# SCH_PCB_sin_SMD-v1_2026-09-21.net
KiCad netlist of a schematic drawn in EasyEDA
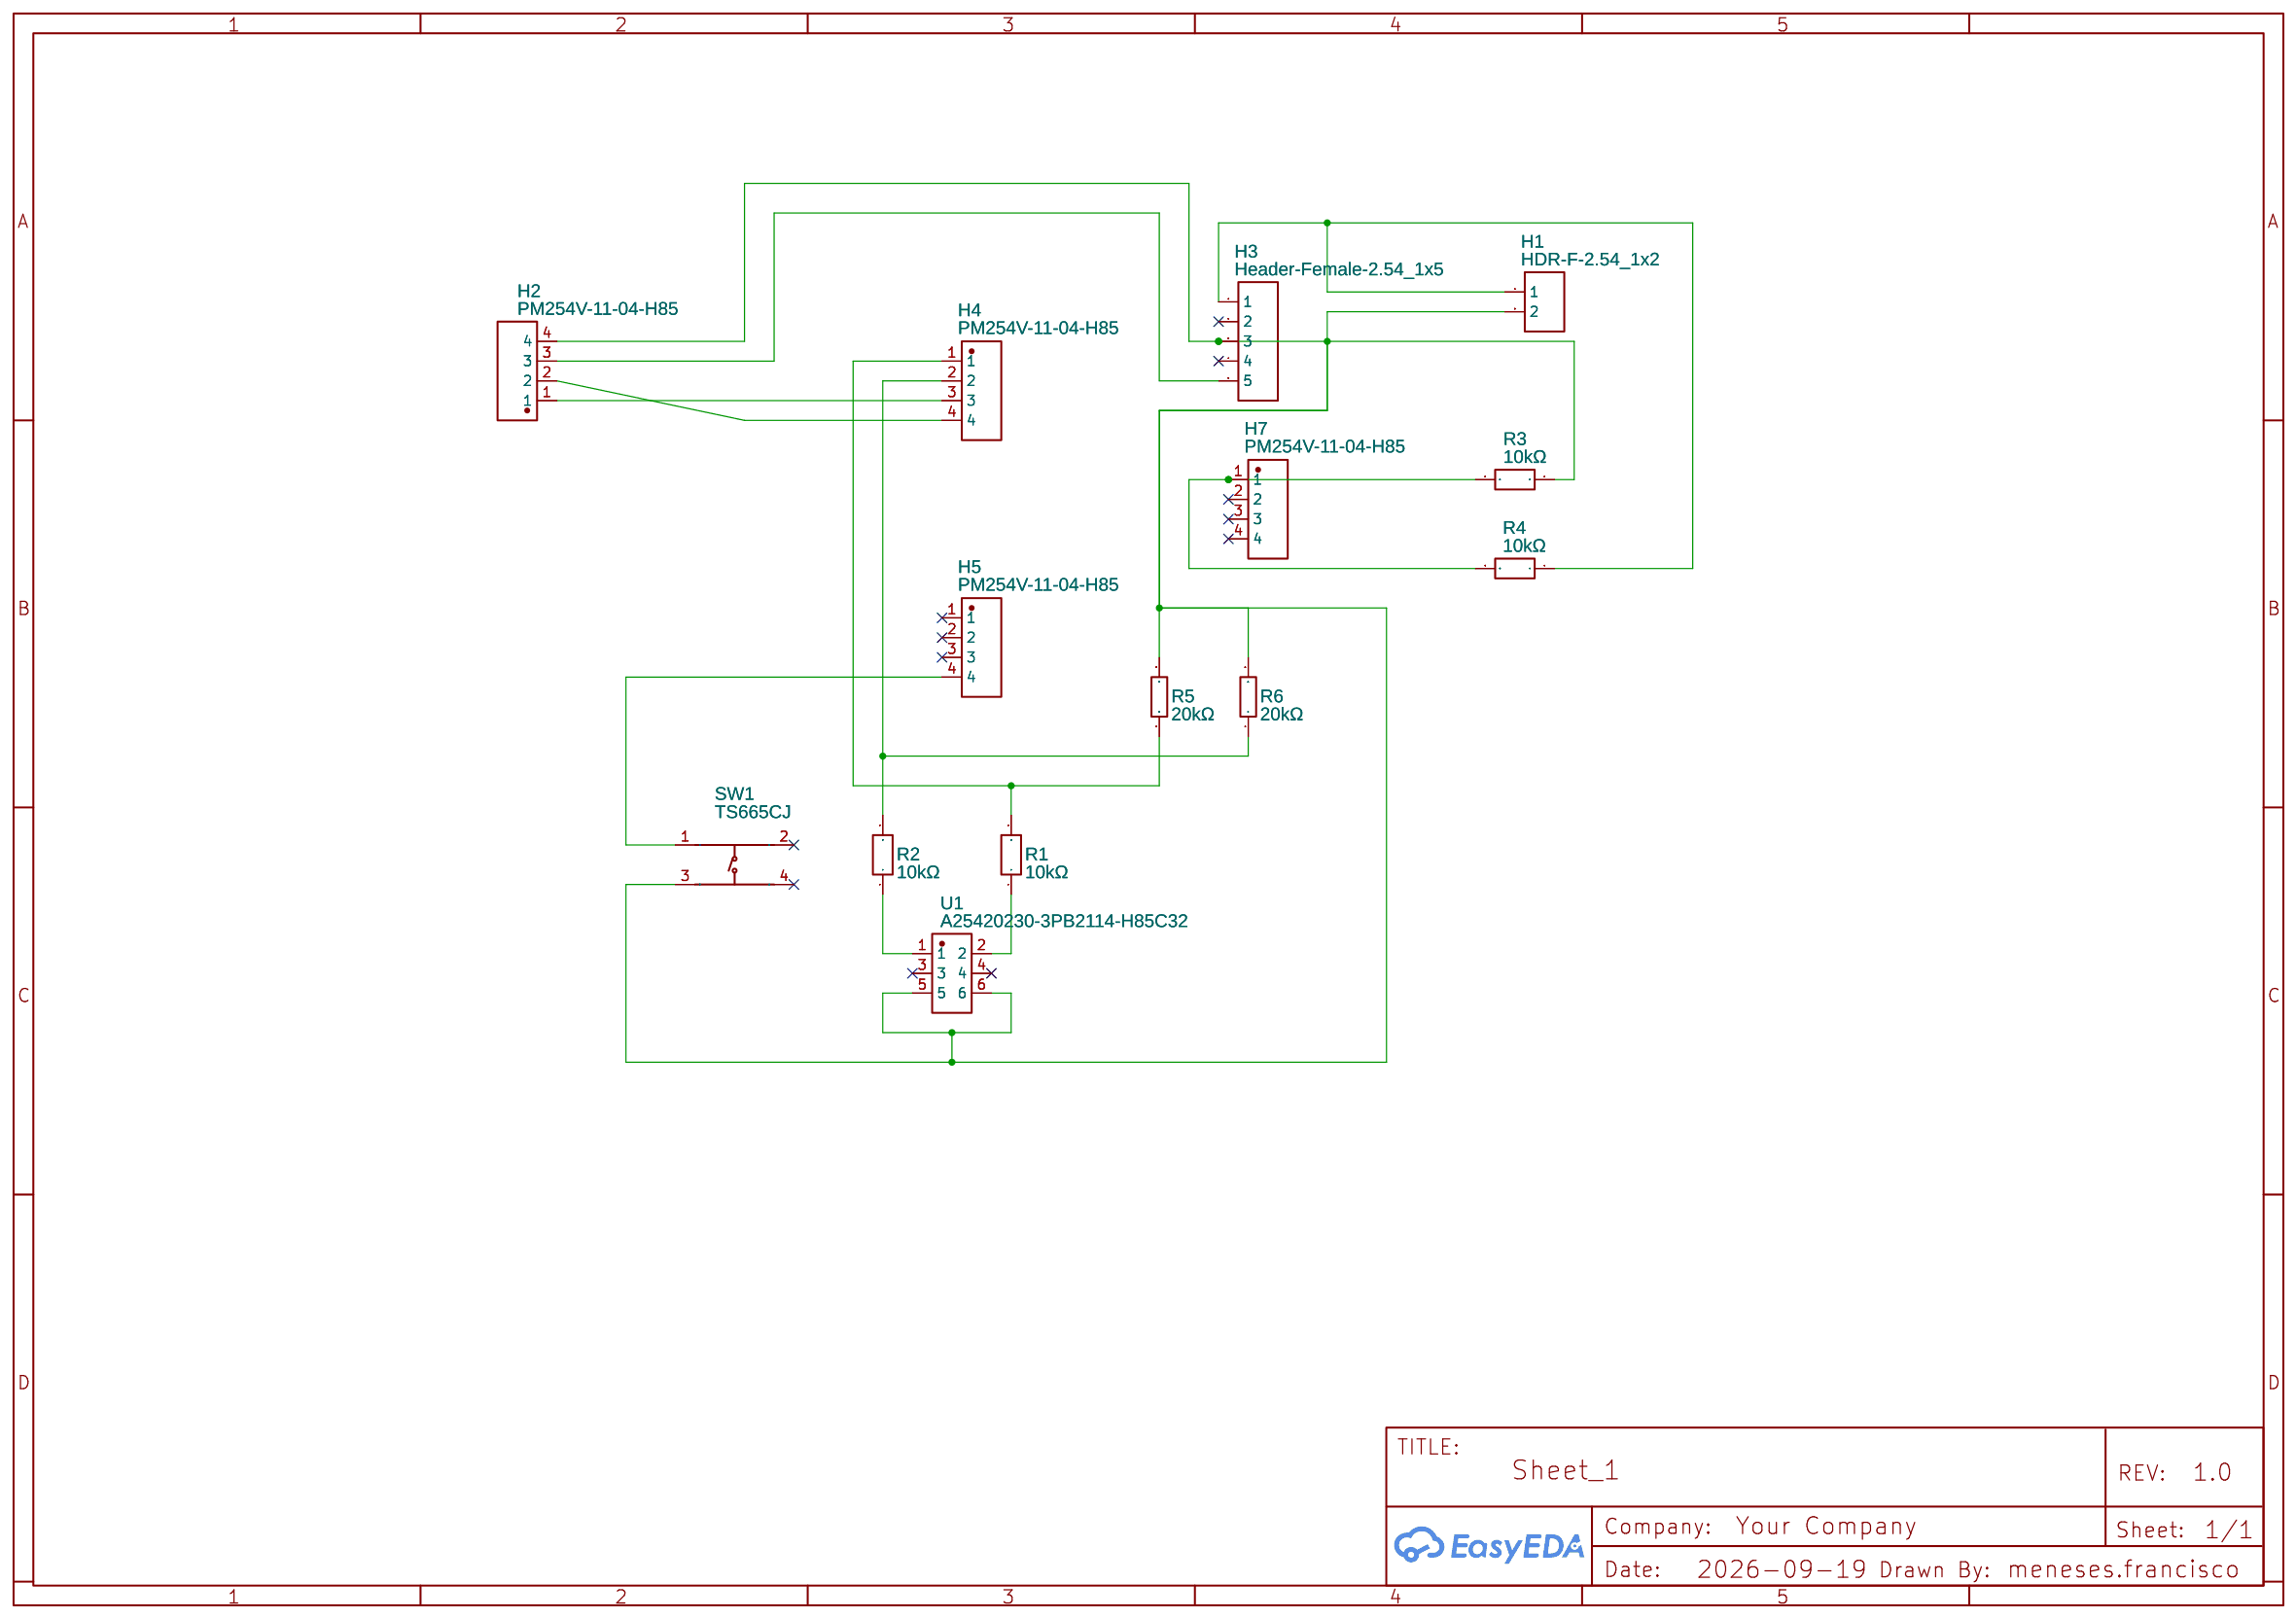
[diagram p0: schematic sheet]

(export (version "E")
  (design (tool "Eeschema 10.0.6"))
  (components
    (comp (ref "H1") (value "HDR-F-2.54_1x2") (libsource (lib "") (part "HDR-F-2.54_1x2")))
    (comp (ref "H2")
      (value "PM254V-11-04-H85")
      (fields (field (name "Manufacturer") "XFCN(兴飞)"))
      (libsource (lib "") (part "PM254V-11-04-H85"))
    )
    (comp (ref "H3")
      (value "Header-Female-2.54_1x5")
      (fields (field (name "Manufacturer Part") "2.54-1*5P母") (field (name "Manufacturer") "BOOMELE(博穆精密)"))
      (libsource (lib "") (part "Header-Female-2.54_1x5"))
    )
    (comp (ref "H4")
      (value "PM254V-11-04-H85")
      (fields (field (name "Manufacturer") "XFCN(兴飞)"))
      (libsource (lib "") (part "PM254V-11-04-H85_1"))
    )
    (comp (ref "H5")
      (value "PM254V-11-04-H85")
      (fields (field (name "Manufacturer") "XFCN(兴飞)"))
      (libsource (lib "") (part "PM254V-11-04-H85_1"))
    )
    (comp (ref "H7")
      (value "PM254V-11-04-H85")
      (fields (field (name "Manufacturer") "XFCN(兴飞)"))
      (libsource (lib "") (part "PM254V-11-04-H85_1"))
    )
    (comp (ref "R1")
      (value "10kΩ")
      (fields (field (name "Manufacturer Part") "MF1/4W-10K±1%-ST52") (field (name "Manufacturer") "VO(翔胜)"))
      (libsource (lib "") (part "MF1/4W-10K±1%-ST52"))
    )
    (comp (ref "R2")
      (value "10kΩ")
      (fields (field (name "Manufacturer Part") "MF1/4W-10K±1%-ST52") (field (name "Manufacturer") "VO(翔胜)"))
      (libsource (lib "") (part "MF1/4W-10K±1%-ST52"))
    )
    (comp (ref "R3")
      (value "10kΩ")
      (fields (field (name "Manufacturer Part") "MF1/4W-10K±1%-ST52") (field (name "Manufacturer") "VO(翔胜)"))
      (libsource (lib "") (part "MF1/4W-10K±1%-ST52_1"))
    )
    (comp (ref "R4")
      (value "10kΩ")
      (fields (field (name "Manufacturer Part") "MF1/4W-10K±1%-ST52") (field (name "Manufacturer") "VO(翔胜)"))
      (libsource (lib "") (part "MF1/4W-10K±1%-ST52_1"))
    )
    (comp (ref "R5")
      (value "20kΩ")
      (fields (field (name "Manufacturer Part") "MF1/4W-20KΩ±1% T") (field (name "Manufacturer") "CCO(千志电子)"))
      (libsource (lib "") (part "MF1/4W-20KΩ±1% T52"))
    )
    (comp (ref "R6")
      (value "20kΩ")
      (fields (field (name "Manufacturer Part") "MF1/4W-20KΩ±1% T") (field (name "Manufacturer") "CCO(千志电子)"))
      (libsource (lib "") (part "MF1/4W-20KΩ±1% T52"))
    )
    (comp (ref "SW1")
      (value "TS665CJ")
      (fields (field (name "Manufacturer") "SHOU HAN(首韩)"))
      (libsource (lib "") (part "TS665CJ"))
    )
    (comp (ref "U1")
      (value "A25420230-3PB2114-H85C32")
      (fields (field (name "Manufacturer") "HMTCONN(华明通)"))
      (libsource (lib "") (part "A25420230-3PB2114-H85C32"))
    )
  )
  (nets
    (net (code "1") (name "Net-(H1-Pad1)") (class "Default")
      (node (ref "H1") (pin "1") (pinfunction "1_1") (pintype "input"))
      (node (ref "H3") (pin "1") (pinfunction "1_1") (pintype "input"))
      (node (ref "R4") (pin "1") (pinfunction "1_1") (pintype "unspecified"))
    )
    (net (code "2") (name "Net-(H2-Pad1)") (class "Default")
      (node (ref "H2") (pin "1") (pinfunction "1_1") (pintype "unspecified"))
      (node (ref "H4") (pin "3") (pinfunction "3_3") (pintype "unspecified"))
    )
    (net (code "3") (name "Net-(H2-Pad2)") (class "Default")
      (node (ref "H2") (pin "2") (pinfunction "2_2") (pintype "unspecified"))
      (node (ref "H4") (pin "4") (pinfunction "4_4") (pintype "unspecified"))
    )
    (net (code "4") (name "Net-(H2-Pad3)") (class "Default")
      (node (ref "H2") (pin "3") (pinfunction "3_3") (pintype "unspecified"))
      (node (ref "H3") (pin "5") (pinfunction "5_5") (pintype "input"))
    )
    (net (code "5") (name "Net-(H4-Pad1)") (class "Default")
      (node (ref "H4") (pin "1") (pinfunction "1_1") (pintype "unspecified"))
      (node (ref "R1") (pin "2") (pinfunction "2_2") (pintype "unspecified"))
      (node (ref "R5") (pin "1") (pinfunction "1_1") (pintype "unspecified"))
    )
    (net (code "6") (name "Net-(H4-Pad2)") (class "Default")
      (node (ref "H4") (pin "2") (pinfunction "2_2") (pintype "unspecified"))
      (node (ref "R2") (pin "2") (pinfunction "2_2") (pintype "unspecified"))
      (node (ref "R6") (pin "1") (pinfunction "1_1") (pintype "unspecified"))
    )
    (net (code "7") (name "Net-(H7-Pad1)") (class "Default")
      (node (ref "H7") (pin "1") (pinfunction "1_1") (pintype "unspecified"))
      (node (ref "R3") (pin "2") (pinfunction "2_2") (pintype "unspecified"))
      (node (ref "R4") (pin "2") (pinfunction "2_2") (pintype "unspecified"))
    )
    (net (code "8") (name "Net-(R1-Pad1)") (class "Default")
      (node (ref "R1") (pin "1") (pinfunction "1_1") (pintype "unspecified"))
      (node (ref "U1") (pin "2") (pinfunction "2_2") (pintype "unspecified"))
    )
    (net (code "9") (name "Net-(R2-Pad1)") (class "Default")
      (node (ref "R2") (pin "1") (pinfunction "1_1") (pintype "unspecified"))
      (node (ref "U1") (pin "1") (pinfunction "1_1") (pintype "unspecified"))
    )
    (net (code "10") (name "Net-(SW1-A)") (class "Default")
      (node (ref "H5") (pin "4") (pinfunction "4_4") (pintype "unspecified"))
      (node (ref "SW1") (pin "1") (pinfunction "A_1") (pintype "unspecified"))
    )
    (net (code "11") (name "Net-(SW1-C)") (class "Default")
      (node (ref "H1") (pin "2") (pinfunction "2_2") (pintype "input"))
      (node (ref "H2") (pin "4") (pinfunction "4_4") (pintype "unspecified"))
      (node (ref "H3") (pin "3") (pinfunction "3_3") (pintype "input"))
      (node (ref "R3") (pin "1") (pinfunction "1_1") (pintype "unspecified"))
      (node (ref "R5") (pin "2") (pinfunction "2_2") (pintype "unspecified"))
      (node (ref "R6") (pin "2") (pinfunction "2_2") (pintype "unspecified"))
      (node (ref "SW1") (pin "3") (pinfunction "C_3") (pintype "unspecified"))
      (node (ref "U1") (pin "5") (pinfunction "5_5") (pintype "unspecified"))
      (node (ref "U1") (pin "6") (pinfunction "6_6") (pintype "unspecified"))
    )
    (net (code "12") (name "unconnected-(H3-Pad2)") (class "Default")
      (node (ref "H3") (pin "2") (pinfunction "2_2") (pintype "input+no_connect"))
    )
    (net (code "13") (name "unconnected-(H3-Pad4)") (class "Default")
      (node (ref "H3") (pin "4") (pinfunction "4_4") (pintype "input+no_connect"))
    )
    (net (code "14") (name "unconnected-(H5-Pad1)") (class "Default")
      (node (ref "H5") (pin "1") (pinfunction "1_1") (pintype "unspecified+no_connect"))
    )
    (net (code "15") (name "unconnected-(H5-Pad2)") (class "Default")
      (node (ref "H5") (pin "2") (pinfunction "2_2") (pintype "unspecified+no_connect"))
    )
    (net (code "16") (name "unconnected-(H5-Pad3)") (class "Default")
      (node (ref "H5") (pin "3") (pinfunction "3_3") (pintype "unspecified+no_connect"))
    )
    (net (code "17") (name "unconnected-(H7-Pad2)") (class "Default")
      (node (ref "H7") (pin "2") (pinfunction "2_2") (pintype "unspecified+no_connect"))
    )
    (net (code "18") (name "unconnected-(H7-Pad3)") (class "Default")
      (node (ref "H7") (pin "3") (pinfunction "3_3") (pintype "unspecified+no_connect"))
    )
    (net (code "19") (name "unconnected-(H7-Pad4)") (class "Default")
      (node (ref "H7") (pin "4") (pinfunction "4_4") (pintype "unspecified+no_connect"))
    )
    (net (code "20") (name "unconnected-(SW1-B-Pad2)") (class "Default")
      (node (ref "SW1") (pin "2") (pinfunction "B_2") (pintype "unspecified+no_connect"))
    )
    (net (code "21") (name "unconnected-(SW1-D-Pad4)") (class "Default")
      (node (ref "SW1") (pin "4") (pinfunction "D_4") (pintype "unspecified+no_connect"))
    )
    (net (code "22") (name "unconnected-(U1-Pad3)") (class "Default")
      (node (ref "U1") (pin "3") (pinfunction "3_3") (pintype "unspecified+no_connect"))
    )
    (net (code "23") (name "unconnected-(U1-Pad4)") (class "Default")
      (node (ref "U1") (pin "4") (pinfunction "4_4") (pintype "unspecified+no_connect"))
    )
  )
)
